# v2.net
KiCad netlist of a schematic drawn in EAGLE
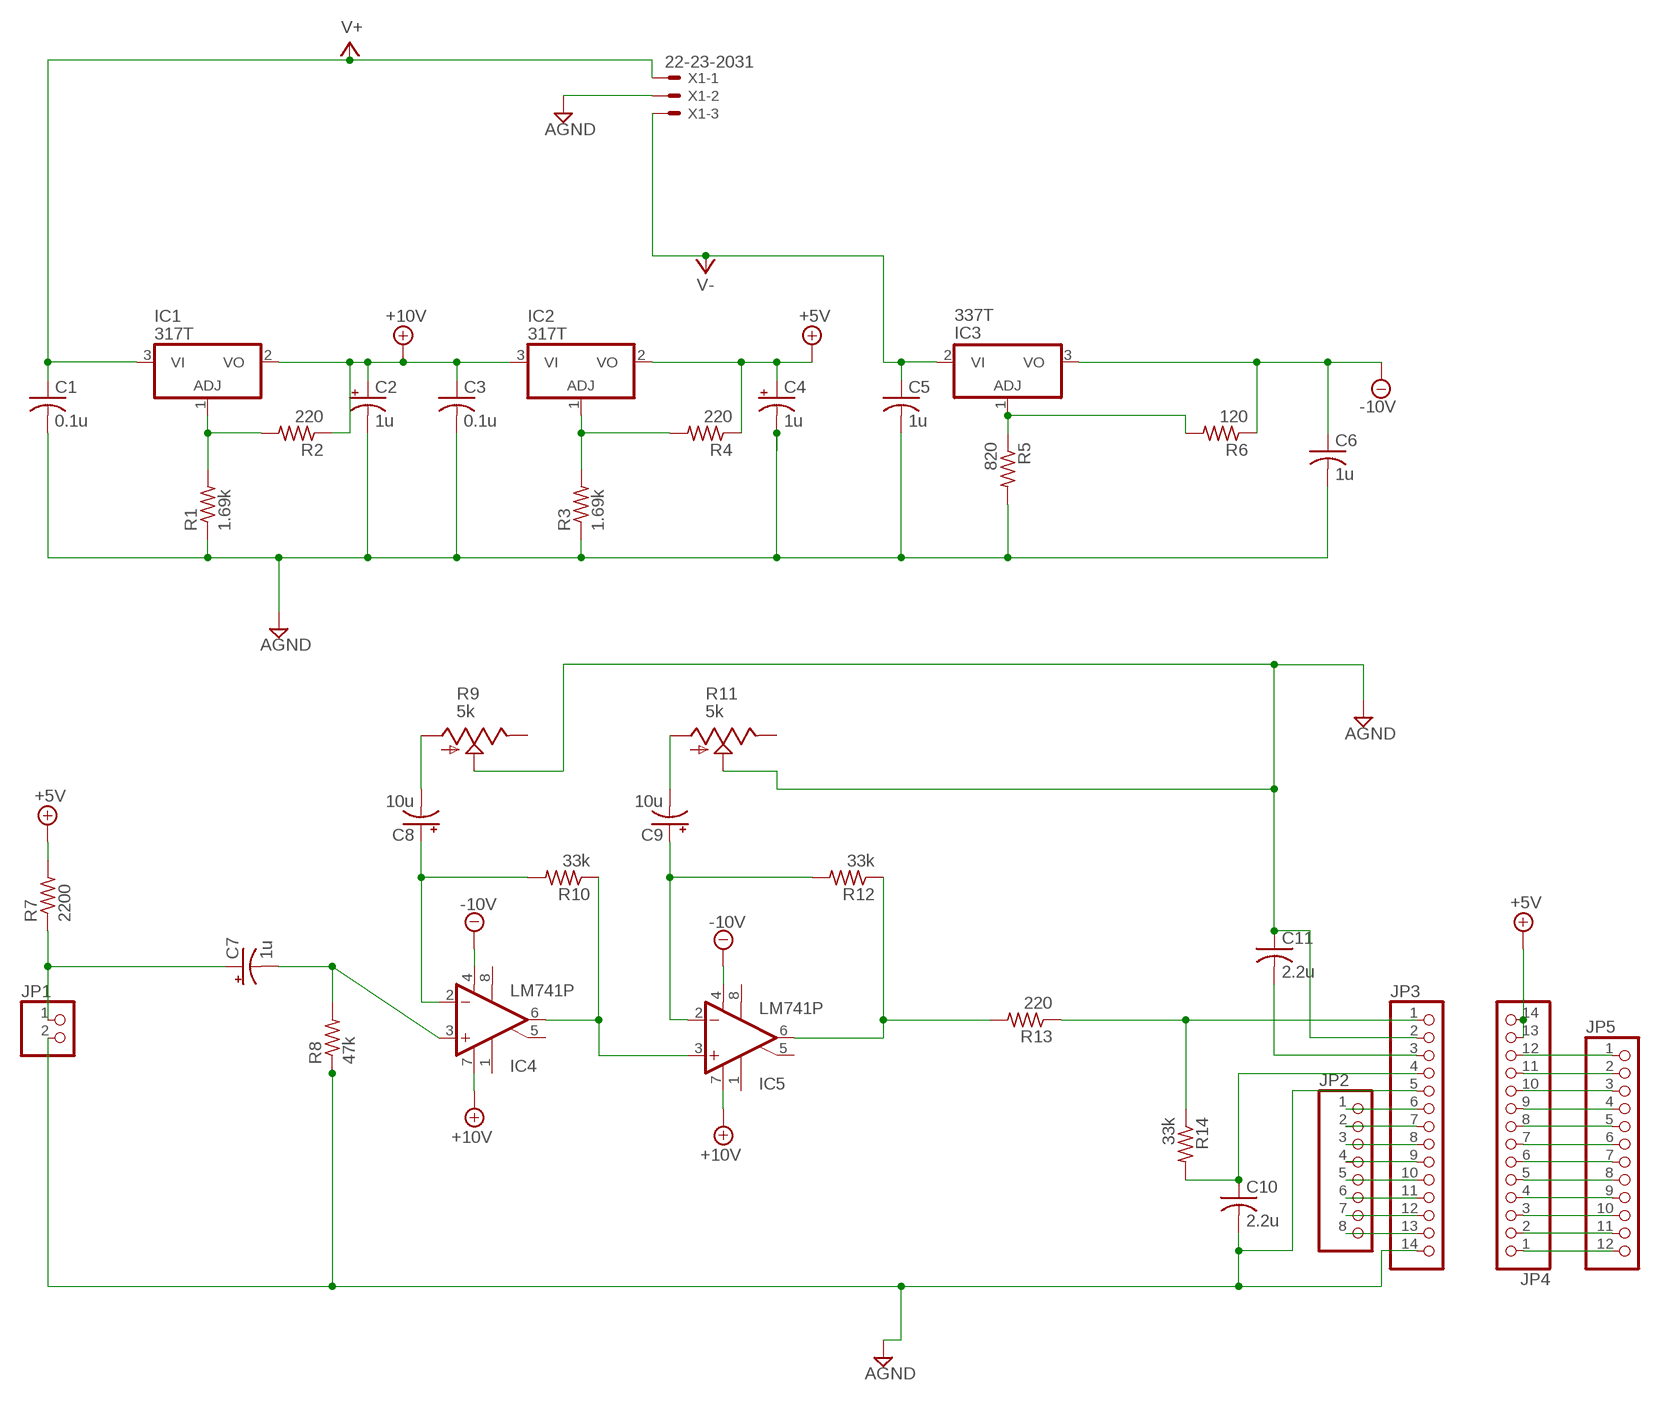
[diagram p0: schematic, sheet 1]

(export (version "E")
  (design (tool "Eeschema 10.0.6"))
  (components
    (comp (ref "C1")
      (value "0.1u")
      (footprint "eagle-import:C050-045X075")
      (libsource (lib "eagle-import") (part "C-US050-045X075"))
    )
    (comp (ref "C2")
      (value "1u")
      (footprint "eagle-import:E2,5-5")
      (libsource (lib "eagle-import") (part "CPOL-USE2.5-5"))
    )
    (comp (ref "C3")
      (value "0.1u")
      (footprint "eagle-import:C050-045X075")
      (libsource (lib "eagle-import") (part "C-US050-045X075"))
    )
    (comp (ref "C4")
      (value "1u")
      (footprint "eagle-import:E2,5-5")
      (libsource (lib "eagle-import") (part "CPOL-USE2.5-5"))
    )
    (comp (ref "C5")
      (value "1u")
      (footprint "eagle-import:C050-045X075")
      (libsource (lib "eagle-import") (part "C-US050-045X075"))
    )
    (comp (ref "C6")
      (value "1u")
      (footprint "eagle-import:C050-045X075")
      (libsource (lib "eagle-import") (part "C-US050-045X075"))
    )
    (comp (ref "C7")
      (value "1u")
      (footprint "eagle-import:E2,5-5")
      (libsource (lib "eagle-import") (part "CPOL-USE2.5-5"))
    )
    (comp (ref "C8")
      (value "10u")
      (footprint "eagle-import:E2,5-5")
      (libsource (lib "eagle-import") (part "CPOL-USE2.5-5"))
    )
    (comp (ref "C9")
      (value "10u")
      (footprint "eagle-import:E2,5-5")
      (libsource (lib "eagle-import") (part "CPOL-USE2.5-5"))
    )
    (comp (ref "C10")
      (value "2.2u")
      (footprint "eagle-import:C050-045X075")
      (libsource (lib "eagle-import") (part "C-US050-045X075"))
    )
    (comp (ref "C11")
      (value "2.2u")
      (footprint "eagle-import:C050-045X075")
      (libsource (lib "eagle-import") (part "C-US050-045X075"))
    )
    (comp (ref "IC1")
      (value "317T")
      (footprint "eagle-import:TO220H")
      (libsource (lib "eagle-import") (part "317T"))
    )
    (comp (ref "IC2")
      (value "317T")
      (footprint "eagle-import:TO220H")
      (libsource (lib "eagle-import") (part "317T"))
    )
    (comp (ref "IC3")
      (value "337T")
      (footprint "eagle-import:TO220H")
      (libsource (lib "eagle-import") (part "337T"))
    )
    (comp (ref "IC4")
      (value "LM741P")
      (footprint "eagle-import:DIL08")
      (libsource (lib "eagle-import") (part "741PLM"))
    )
    (comp (ref "IC5")
      (value "LM741P")
      (footprint "eagle-import:DIL08")
      (libsource (lib "eagle-import") (part "741PLM"))
    )
    (comp (ref "JP1")
      (value "PINHD-1X2")
      (footprint "eagle-import:1X02")
      (libsource (lib "eagle-import") (part "PINHD-1X2"))
    )
    (comp (ref "JP2")
      (value "PINHD-1X8")
      (footprint "eagle-import:1X08")
      (libsource (lib "eagle-import") (part "PINHD-1X8"))
    )
    (comp (ref "JP3")
      (value "PINHD-1X14")
      (footprint "eagle-import:1X14")
      (libsource (lib "eagle-import") (part "PINHD-1X14"))
    )
    (comp (ref "JP4")
      (value "PINHD-1X14")
      (footprint "eagle-import:1X14")
      (libsource (lib "eagle-import") (part "PINHD-1X14"))
    )
    (comp (ref "JP5")
      (value "PINHD-1X12")
      (footprint "eagle-import:1X12")
      (libsource (lib "eagle-import") (part "PINHD-1X12"))
    )
    (comp (ref "R1")
      (value "1.69k")
      (footprint "eagle-import:0207_10")
      (libsource (lib "eagle-import") (part "R-US_0207/10"))
    )
    (comp (ref "R2")
      (value "220")
      (footprint "eagle-import:0207_10")
      (libsource (lib "eagle-import") (part "R-US_0207/10"))
    )
    (comp (ref "R3")
      (value "1.69k")
      (footprint "eagle-import:0207_10")
      (libsource (lib "eagle-import") (part "R-US_0207/10"))
    )
    (comp (ref "R4")
      (value "220")
      (footprint "eagle-import:0207_10")
      (libsource (lib "eagle-import") (part "R-US_0207/10"))
    )
    (comp (ref "R5")
      (value "820")
      (footprint "eagle-import:0207_10")
      (libsource (lib "eagle-import") (part "R-US_0207/10"))
    )
    (comp (ref "R6")
      (value "120")
      (footprint "eagle-import:0207_10")
      (libsource (lib "eagle-import") (part "R-US_0207/10"))
    )
    (comp (ref "R7")
      (value "2200")
      (footprint "eagle-import:0207_10")
      (libsource (lib "eagle-import") (part "R-US_0207/10"))
    )
    (comp (ref "R8")
      (value "47k")
      (footprint "eagle-import:0207_10")
      (libsource (lib "eagle-import") (part "R-US_0207/10"))
    )
    (comp (ref "R9")
      (value "5k")
      (footprint "eagle-import:CA6V")
      (libsource (lib "eagle-import") (part "TRIM_US-CA6V"))
    )
    (comp (ref "R10")
      (value "33k")
      (footprint "eagle-import:0207_10")
      (libsource (lib "eagle-import") (part "R-US_0207/10"))
    )
    (comp (ref "R11")
      (value "5k")
      (footprint "eagle-import:CA6V")
      (libsource (lib "eagle-import") (part "TRIM_US-CA6V"))
    )
    (comp (ref "R12")
      (value "33k")
      (footprint "eagle-import:0207_10")
      (libsource (lib "eagle-import") (part "R-US_0207/10"))
    )
    (comp (ref "R13")
      (value "220")
      (footprint "eagle-import:0207_10")
      (libsource (lib "eagle-import") (part "R-US_0207/10"))
    )
    (comp (ref "R14")
      (value "33k")
      (footprint "eagle-import:0207_10")
      (libsource (lib "eagle-import") (part "R-US_0207/10"))
    )
    (comp (ref "X1")
      (value "22-23-2031")
      (footprint "eagle-import:22-23-2031")
      (fields (field (name "MF") "MOLEX"))
      (libsource (lib "eagle-import") (part "22-23-2031"))
    )
  )
  (nets
    (net (code "1") (name "+5V") (class "Default")
      (node (ref "C4") (pin "+") (pinfunction "+_+") (pintype "passive"))
      (node (ref "IC2") (pin "2") (pinfunction "VO_2") (pintype "passive"))
      (node (ref "JP4") (pin "13") (pinfunction "13_13") (pintype "passive"))
      (node (ref "JP4") (pin "14") (pinfunction "14_14") (pintype "passive"))
      (node (ref "R4") (pin "1") (pinfunction "1_1") (pintype "passive"))
      (node (ref "R7") (pin "2") (pinfunction "2_2") (pintype "passive"))
    )
    (net (code "2") (name "+10V") (class "Default")
      (node (ref "C2") (pin "+") (pinfunction "+_+") (pintype "passive"))
      (node (ref "C3") (pin "1") (pinfunction "1_1") (pintype "passive"))
      (node (ref "IC1") (pin "2") (pinfunction "VO_2") (pintype "passive"))
      (node (ref "IC2") (pin "3") (pinfunction "VI_3") (pintype "input"))
      (node (ref "IC4") (pin "7") (pinfunction "V+_7") (pintype "power_in"))
      (node (ref "IC5") (pin "7") (pinfunction "V+_7") (pintype "power_in"))
      (node (ref "R2") (pin "1") (pinfunction "1_1") (pintype "passive"))
    )
    (net (code "3") (name "-10V") (class "Default")
      (node (ref "C6") (pin "1") (pinfunction "1_1") (pintype "passive"))
      (node (ref "IC3") (pin "3") (pinfunction "VO_3") (pintype "passive"))
      (node (ref "IC4") (pin "4") (pinfunction "V-_4") (pintype "power_in"))
      (node (ref "IC5") (pin "4") (pinfunction "V-_4") (pintype "power_in"))
      (node (ref "R6") (pin "1") (pinfunction "1_1") (pintype "passive"))
    )
    (net (code "4") (name "AGND") (class "Default")
      (node (ref "C1") (pin "2") (pinfunction "2_2") (pintype "passive"))
      (node (ref "C10") (pin "2") (pinfunction "2_2") (pintype "passive"))
      (node (ref "C11") (pin "1") (pinfunction "1_1") (pintype "passive"))
      (node (ref "C2") (pin "-") (pinfunction "-_-") (pintype "passive"))
      (node (ref "C3") (pin "2") (pinfunction "2_2") (pintype "passive"))
      (node (ref "C4") (pin "-") (pinfunction "-_-") (pintype "passive"))
      (node (ref "C5") (pin "2") (pinfunction "2_2") (pintype "passive"))
      (node (ref "C6") (pin "2") (pinfunction "2_2") (pintype "passive"))
      (node (ref "JP1") (pin "2") (pinfunction "2_2") (pintype "passive"))
      (node (ref "JP3") (pin "14") (pinfunction "14_14") (pintype "passive"))
      (node (ref "JP3") (pin "2") (pinfunction "2_2") (pintype "passive"))
      (node (ref "JP3") (pin "5") (pinfunction "5_5") (pintype "passive"))
      (node (ref "R1") (pin "1") (pinfunction "1_1") (pintype "passive"))
      (node (ref "R11") (pin "S") (pinfunction "S_S") (pintype "passive"))
      (node (ref "R3") (pin "1") (pinfunction "1_1") (pintype "passive"))
      (node (ref "R5") (pin "2") (pinfunction "2_2") (pintype "passive"))
      (node (ref "R8") (pin "1") (pinfunction "1_1") (pintype "passive"))
      (node (ref "R9") (pin "S") (pinfunction "S_S") (pintype "passive"))
      (node (ref "X1") (pin "2") (pinfunction "S_2") (pintype "passive"))
    )
    (net (code "5") (name "Net-(C7-Pad+)") (class "Default")
      (node (ref "C7") (pin "+") (pinfunction "+_+") (pintype "passive"))
      (node (ref "JP1") (pin "1") (pinfunction "1_1") (pintype "passive"))
      (node (ref "R7") (pin "1") (pinfunction "1_1") (pintype "passive"))
    )
    (net (code "6") (name "Net-(C8-Pad-)") (class "Default")
      (node (ref "C8") (pin "-") (pinfunction "-_-") (pintype "passive"))
      (node (ref "R9") (pin "A") (pinfunction "A_A") (pintype "passive"))
    )
    (net (code "7") (name "Net-(C9-Pad-)") (class "Default")
      (node (ref "C9") (pin "-") (pinfunction "-_-") (pintype "passive"))
      (node (ref "R11") (pin "A") (pinfunction "A_A") (pintype "passive"))
    )
    (net (code "8") (name "Net-(C10-Pad1)") (class "Default")
      (node (ref "C10") (pin "1") (pinfunction "1_1") (pintype "passive"))
      (node (ref "JP3") (pin "4") (pinfunction "4_4") (pintype "passive"))
      (node (ref "R14") (pin "2") (pinfunction "2_2") (pintype "passive"))
    )
    (net (code "9") (name "Net-(C11-Pad2)") (class "Default")
      (node (ref "C11") (pin "2") (pinfunction "2_2") (pintype "passive"))
      (node (ref "JP3") (pin "3") (pinfunction "3_3") (pintype "passive"))
    )
    (net (code "10") (name "Net-(IC1-ADJ)") (class "Default")
      (node (ref "IC1") (pin "1") (pinfunction "ADJ_1") (pintype "input"))
      (node (ref "R1") (pin "2") (pinfunction "2_2") (pintype "passive"))
      (node (ref "R2") (pin "2") (pinfunction "2_2") (pintype "passive"))
    )
    (net (code "11") (name "Net-(IC2-ADJ)") (class "Default")
      (node (ref "IC2") (pin "1") (pinfunction "ADJ_1") (pintype "input"))
      (node (ref "R3") (pin "2") (pinfunction "2_2") (pintype "passive"))
      (node (ref "R4") (pin "2") (pinfunction "2_2") (pintype "passive"))
    )
    (net (code "12") (name "Net-(IC3-ADJ)") (class "Default")
      (node (ref "IC3") (pin "1") (pinfunction "ADJ_1") (pintype "input"))
      (node (ref "R5") (pin "1") (pinfunction "1_1") (pintype "passive"))
      (node (ref "R6") (pin "2") (pinfunction "2_2") (pintype "passive"))
    )
    (net (code "13") (name "Net-(IC4-+IN)") (class "Default")
      (node (ref "C7") (pin "-") (pinfunction "-_-") (pintype "passive"))
      (node (ref "IC4") (pin "3") (pinfunction "+IN_3") (pintype "input"))
      (node (ref "R8") (pin "2") (pinfunction "2_2") (pintype "passive"))
    )
    (net (code "14") (name "Net-(IC4--IN)") (class "Default")
      (node (ref "C8") (pin "+") (pinfunction "+_+") (pintype "passive"))
      (node (ref "IC4") (pin "2") (pinfunction "-IN_2") (pintype "input"))
      (node (ref "R10") (pin "2") (pinfunction "2_2") (pintype "passive"))
    )
    (net (code "15") (name "Net-(IC4-OUT)") (class "Default")
      (node (ref "IC4") (pin "6") (pinfunction "OUT_6") (pintype "output"))
      (node (ref "IC5") (pin "3") (pinfunction "+IN_3") (pintype "input"))
      (node (ref "R10") (pin "1") (pinfunction "1_1") (pintype "passive"))
    )
    (net (code "16") (name "Net-(IC5--IN)") (class "Default")
      (node (ref "C9") (pin "+") (pinfunction "+_+") (pintype "passive"))
      (node (ref "IC5") (pin "2") (pinfunction "-IN_2") (pintype "input"))
      (node (ref "R12") (pin "2") (pinfunction "2_2") (pintype "passive"))
    )
    (net (code "17") (name "Net-(IC5-OUT)") (class "Default")
      (node (ref "IC5") (pin "6") (pinfunction "OUT_6") (pintype "output"))
      (node (ref "R12") (pin "1") (pinfunction "1_1") (pintype "passive"))
      (node (ref "R13") (pin "2") (pinfunction "2_2") (pintype "passive"))
    )
    (net (code "18") (name "Net-(JP2-Pad1)") (class "Default")
      (node (ref "JP2") (pin "1") (pinfunction "1_1") (pintype "passive"))
      (node (ref "JP3") (pin "6") (pinfunction "6_6") (pintype "passive"))
    )
    (net (code "19") (name "Net-(JP2-Pad2)") (class "Default")
      (node (ref "JP2") (pin "2") (pinfunction "2_2") (pintype "passive"))
      (node (ref "JP3") (pin "7") (pinfunction "7_7") (pintype "passive"))
    )
    (net (code "20") (name "Net-(JP2-Pad3)") (class "Default")
      (node (ref "JP2") (pin "3") (pinfunction "3_3") (pintype "passive"))
      (node (ref "JP3") (pin "8") (pinfunction "8_8") (pintype "passive"))
    )
    (net (code "21") (name "Net-(JP2-Pad4)") (class "Default")
      (node (ref "JP2") (pin "4") (pinfunction "4_4") (pintype "passive"))
      (node (ref "JP3") (pin "9") (pinfunction "9_9") (pintype "passive"))
    )
    (net (code "22") (name "Net-(JP2-Pad5)") (class "Default")
      (node (ref "JP2") (pin "5") (pinfunction "5_5") (pintype "passive"))
      (node (ref "JP3") (pin "10") (pinfunction "10_10") (pintype "passive"))
    )
    (net (code "23") (name "Net-(JP2-Pad6)") (class "Default")
      (node (ref "JP2") (pin "6") (pinfunction "6_6") (pintype "passive"))
      (node (ref "JP3") (pin "11") (pinfunction "11_11") (pintype "passive"))
    )
    (net (code "24") (name "Net-(JP2-Pad7)") (class "Default")
      (node (ref "JP2") (pin "7") (pinfunction "7_7") (pintype "passive"))
      (node (ref "JP3") (pin "12") (pinfunction "12_12") (pintype "passive"))
    )
    (net (code "25") (name "Net-(JP2-Pad8)") (class "Default")
      (node (ref "JP2") (pin "8") (pinfunction "8_8") (pintype "passive"))
      (node (ref "JP3") (pin "13") (pinfunction "13_13") (pintype "passive"))
    )
    (net (code "26") (name "Net-(JP3-Pad1)") (class "Default")
      (node (ref "JP3") (pin "1") (pinfunction "1_1") (pintype "passive"))
      (node (ref "R13") (pin "1") (pinfunction "1_1") (pintype "passive"))
      (node (ref "R14") (pin "1") (pinfunction "1_1") (pintype "passive"))
    )
    (net (code "27") (name "Net-(JP4-Pad1)") (class "Default")
      (node (ref "JP4") (pin "1") (pinfunction "1_1") (pintype "passive"))
      (node (ref "JP5") (pin "12") (pinfunction "12_12") (pintype "passive"))
    )
    (net (code "28") (name "Net-(JP4-Pad2)") (class "Default")
      (node (ref "JP4") (pin "2") (pinfunction "2_2") (pintype "passive"))
      (node (ref "JP5") (pin "11") (pinfunction "11_11") (pintype "passive"))
    )
    (net (code "29") (name "Net-(JP4-Pad3)") (class "Default")
      (node (ref "JP4") (pin "3") (pinfunction "3_3") (pintype "passive"))
      (node (ref "JP5") (pin "10") (pinfunction "10_10") (pintype "passive"))
    )
    (net (code "30") (name "Net-(JP4-Pad4)") (class "Default")
      (node (ref "JP4") (pin "4") (pinfunction "4_4") (pintype "passive"))
      (node (ref "JP5") (pin "9") (pinfunction "9_9") (pintype "passive"))
    )
    (net (code "31") (name "Net-(JP4-Pad5)") (class "Default")
      (node (ref "JP4") (pin "5") (pinfunction "5_5") (pintype "passive"))
      (node (ref "JP5") (pin "8") (pinfunction "8_8") (pintype "passive"))
    )
    (net (code "32") (name "Net-(JP4-Pad6)") (class "Default")
      (node (ref "JP4") (pin "6") (pinfunction "6_6") (pintype "passive"))
      (node (ref "JP5") (pin "7") (pinfunction "7_7") (pintype "passive"))
    )
    (net (code "33") (name "Net-(JP4-Pad7)") (class "Default")
      (node (ref "JP4") (pin "7") (pinfunction "7_7") (pintype "passive"))
      (node (ref "JP5") (pin "6") (pinfunction "6_6") (pintype "passive"))
    )
    (net (code "34") (name "Net-(JP4-Pad8)") (class "Default")
      (node (ref "JP4") (pin "8") (pinfunction "8_8") (pintype "passive"))
      (node (ref "JP5") (pin "5") (pinfunction "5_5") (pintype "passive"))
    )
    (net (code "35") (name "Net-(JP4-Pad9)") (class "Default")
      (node (ref "JP4") (pin "9") (pinfunction "9_9") (pintype "passive"))
      (node (ref "JP5") (pin "4") (pinfunction "4_4") (pintype "passive"))
    )
    (net (code "36") (name "Net-(JP4-Pad10)") (class "Default")
      (node (ref "JP4") (pin "10") (pinfunction "10_10") (pintype "passive"))
      (node (ref "JP5") (pin "3") (pinfunction "3_3") (pintype "passive"))
    )
    (net (code "37") (name "Net-(JP4-Pad11)") (class "Default")
      (node (ref "JP4") (pin "11") (pinfunction "11_11") (pintype "passive"))
      (node (ref "JP5") (pin "2") (pinfunction "2_2") (pintype "passive"))
    )
    (net (code "38") (name "Net-(JP4-Pad12)") (class "Default")
      (node (ref "JP4") (pin "12") (pinfunction "12_12") (pintype "passive"))
      (node (ref "JP5") (pin "1") (pinfunction "1_1") (pintype "passive"))
    )
    (net (code "39") (name "V+") (class "Default")
      (node (ref "C1") (pin "1") (pinfunction "1_1") (pintype "passive"))
      (node (ref "IC1") (pin "3") (pinfunction "VI_3") (pintype "input"))
      (node (ref "X1") (pin "1") (pinfunction "S_1") (pintype "passive"))
    )
    (net (code "40") (name "V-") (class "Default")
      (node (ref "C5") (pin "1") (pinfunction "1_1") (pintype "passive"))
      (node (ref "IC3") (pin "2") (pinfunction "VI_2") (pintype "input"))
      (node (ref "X1") (pin "3") (pinfunction "S_3") (pintype "passive"))
    )
    (net (code "41") (name "unconnected-(IC4-ON1-Pad1)") (class "Default")
      (node (ref "IC4") (pin "1") (pinfunction "ON1_1") (pintype "passive"))
    )
    (net (code "42") (name "unconnected-(IC4-ON2-Pad5)") (class "Default")
      (node (ref "IC4") (pin "5") (pinfunction "ON2_5") (pintype "passive"))
    )
    (net (code "43") (name "unconnected-(IC4-OPT-Pad8)") (class "Default")
      (node (ref "IC4") (pin "8") (pinfunction "OPT_8") (pintype "passive"))
    )
    (net (code "44") (name "unconnected-(IC5-ON1-Pad1)") (class "Default")
      (node (ref "IC5") (pin "1") (pinfunction "ON1_1") (pintype "passive"))
    )
    (net (code "45") (name "unconnected-(IC5-ON2-Pad5)") (class "Default")
      (node (ref "IC5") (pin "5") (pinfunction "ON2_5") (pintype "passive"))
    )
    (net (code "46") (name "unconnected-(IC5-OPT-Pad8)") (class "Default")
      (node (ref "IC5") (pin "8") (pinfunction "OPT_8") (pintype "passive"))
    )
    (net (code "47") (name "unconnected-(R9-PadE)") (class "Default")
      (node (ref "R9") (pin "E") (pinfunction "E_E") (pintype "passive"))
    )
    (net (code "48") (name "unconnected-(R11-PadE)") (class "Default")
      (node (ref "R11") (pin "E") (pinfunction "E_E") (pintype "passive"))
    )
  )
)
